# IO.net
KiCad netlist of a schematic drawn in Altium Designer
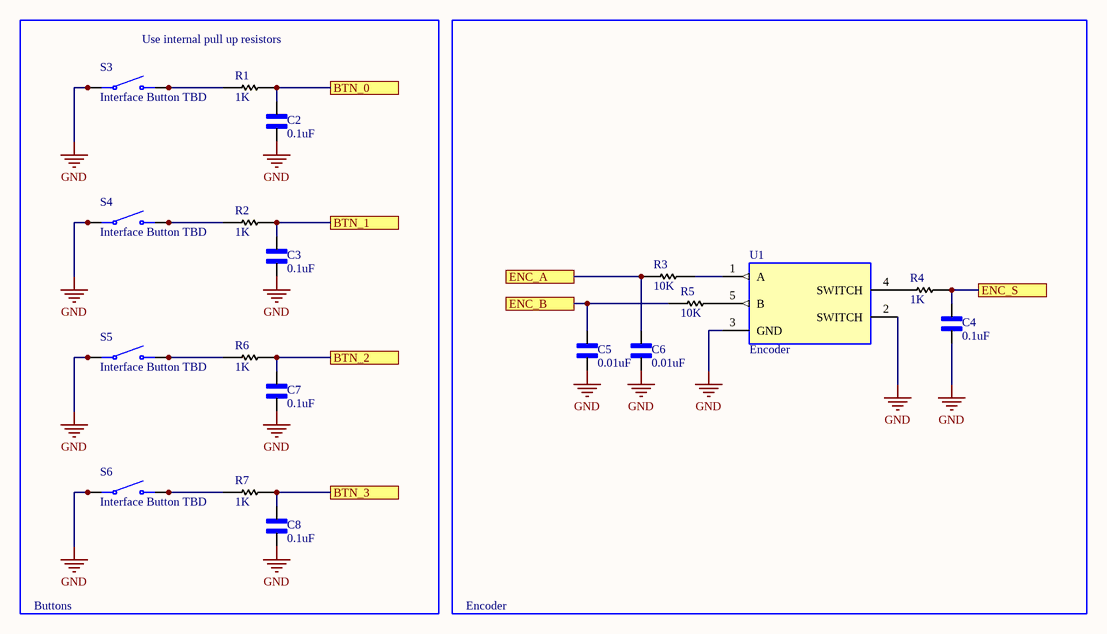
[diagram p0: IO.SchDoc]

(export (version "E")
  (design (tool "Eeschema 10.0.6"))
  (components
    (comp (ref "C2")
      (value "0.1uF")
      (footprint "CHIP_0603")
      (description "Generic 0603 Ceramic Capacitor")
      (fields (field (name "MP") "AC0402FR-071ML") (field (name "MF") "Yageo"))
      (libsource (lib "Guitar_Multi_Effect_Interface_lib") (part "0603 Ceramic Capacitor"))
    )
    (comp (ref "C3")
      (value "0.1uF")
      (footprint "CHIP_0603")
      (description "Generic 0603 Ceramic Capacitor")
      (fields (field (name "MP") "AC0402FR-071ML") (field (name "MF") "Yageo"))
      (libsource (lib "Guitar_Multi_Effect_Interface_lib") (part "0603 Ceramic Capacitor"))
    )
    (comp (ref "C4")
      (value "0.1uF")
      (footprint "CHIP_0603")
      (description "Generic 0603 Ceramic Capacitor")
      (fields (field (name "MP") "AC0402FR-071ML") (field (name "MF") "Yageo"))
      (libsource (lib "Guitar_Multi_Effect_Interface_lib") (part "0603 Ceramic Capacitor"))
    )
    (comp (ref "C5")
      (value "0.01uF")
      (footprint "CHIP_0603")
      (description "Generic 0603 Ceramic Capacitor")
      (fields (field (name "MP") "AC0402FR-071ML") (field (name "MF") "Yageo"))
      (libsource (lib "Guitar_Multi_Effect_Interface_lib") (part "0603 Ceramic Capacitor"))
    )
    (comp (ref "C6")
      (value "0.01uF")
      (footprint "CHIP_0603")
      (description "Generic 0603 Ceramic Capacitor")
      (fields (field (name "MP") "AC0402FR-071ML") (field (name "MF") "Yageo"))
      (libsource (lib "Guitar_Multi_Effect_Interface_lib") (part "0603 Ceramic Capacitor"))
    )
    (comp (ref "C7")
      (value "0.1uF")
      (footprint "CHIP_0603")
      (description "Generic 0603 Ceramic Capacitor")
      (fields (field (name "MP") "AC0402FR-071ML") (field (name "MF") "Yageo"))
      (libsource (lib "Guitar_Multi_Effect_Interface_lib") (part "0603 Ceramic Capacitor"))
    )
    (comp (ref "C8")
      (value "0.1uF")
      (footprint "CHIP_0603")
      (description "Generic 0603 Ceramic Capacitor")
      (fields (field (name "MP") "AC0402FR-071ML") (field (name "MF") "Yageo"))
      (libsource (lib "Guitar_Multi_Effect_Interface_lib") (part "0603 Ceramic Capacitor"))
    )
    (comp (ref "R1")
      (value "1K")
      (footprint "CHIP_R_0603")
      (description "Generic 0603 Resistor")
      (libsource (lib "Guitar_Multi_Effect_Interface_lib") (part "0603 Generic Resistor"))
    )
    (comp (ref "R2")
      (value "1K")
      (footprint "CHIP_R_0603")
      (description "Generic 0603 Resistor")
      (libsource (lib "Guitar_Multi_Effect_Interface_lib") (part "0603 Generic Resistor"))
    )
    (comp (ref "R3")
      (value "10K")
      (footprint "CHIP_R_0603")
      (description "Generic 0603 Resistor")
      (libsource (lib "Guitar_Multi_Effect_Interface_lib") (part "0603 Generic Resistor"))
    )
    (comp (ref "R4")
      (value "1K")
      (footprint "CHIP_R_0603")
      (description "Generic 0603 Resistor")
      (libsource (lib "Guitar_Multi_Effect_Interface_lib") (part "0603 Generic Resistor"))
    )
    (comp (ref "R5")
      (value "10K")
      (footprint "CHIP_R_0603")
      (description "Generic 0603 Resistor")
      (libsource (lib "Guitar_Multi_Effect_Interface_lib") (part "0603 Generic Resistor"))
    )
    (comp (ref "R6")
      (value "1K")
      (footprint "CHIP_R_0603")
      (description "Generic 0603 Resistor")
      (libsource (lib "Guitar_Multi_Effect_Interface_lib") (part "0603 Generic Resistor"))
    )
    (comp (ref "R7")
      (value "1K")
      (footprint "CHIP_R_0603")
      (description "Generic 0603 Resistor")
      (libsource (lib "Guitar_Multi_Effect_Interface_lib") (part "0603 Generic Resistor"))
    )
    (comp (ref "S3")
      (value "Interface Button TBD")
      (footprint "Interface_Button_Multi_Footprint")
      (description "TBD")
      (libsource (lib "Guitar_Multi_Effect_Interface_lib") (part "Interface Button TBD"))
    )
    (comp (ref "S4")
      (value "Interface Button TBD")
      (footprint "Interface_Button_Multi_Footprint")
      (description "TBD")
      (libsource (lib "Guitar_Multi_Effect_Interface_lib") (part "Interface Button TBD"))
    )
    (comp (ref "S5")
      (value "Interface Button TBD")
      (footprint "Interface_Button_Multi_Footprint")
      (description "TBD")
      (libsource (lib "Guitar_Multi_Effect_Interface_lib") (part "Interface Button TBD"))
    )
    (comp (ref "S6")
      (value "Interface Button TBD")
      (footprint "Interface_Button_Multi_Footprint")
      (description "TBD")
      (libsource (lib "Guitar_Multi_Effect_Interface_lib") (part "Interface Button TBD"))
    )
    (comp (ref "U1")
      (value "Encoder")
      (footprint "Encoder Solder Pads")
      (description "Encoder solder connections for PEC11R-4215F-S0024")
      (fields (field (name "MF") "Diodes Inc.") (field (name "MP") "AP3012KTR-G1"))
      (libsource (lib "Guitar_Multi_Effect_Interface_lib") (part "Encoder"))
    )
  )
  (nets
    (net (code "1") (name "/BTN_0") (class "Default")
      (node (ref "C2") (pin "1") (pinfunction "1_1") (pintype "passive"))
      (node (ref "R1") (pin "1") (pinfunction "1_1") (pintype "passive"))
    )
    (net (code "2") (name "/BTN_1") (class "Default")
      (node (ref "C3") (pin "1") (pinfunction "1_1") (pintype "passive"))
      (node (ref "R2") (pin "1") (pinfunction "1_1") (pintype "passive"))
    )
    (net (code "3") (name "/BTN_2") (class "Default")
      (node (ref "C7") (pin "1") (pinfunction "1_1") (pintype "passive"))
      (node (ref "R6") (pin "1") (pinfunction "1_1") (pintype "passive"))
    )
    (net (code "4") (name "/BTN_3") (class "Default")
      (node (ref "C8") (pin "1") (pinfunction "1_1") (pintype "passive"))
      (node (ref "R7") (pin "1") (pinfunction "1_1") (pintype "passive"))
    )
    (net (code "5") (name "/ENC_A") (class "Default")
      (node (ref "C6") (pin "1") (pinfunction "1_1") (pintype "passive"))
      (node (ref "R3") (pin "2") (pinfunction "2_2") (pintype "passive"))
    )
    (net (code "6") (name "/ENC_B") (class "Default")
      (node (ref "C5") (pin "1") (pinfunction "1_1") (pintype "passive"))
      (node (ref "R5") (pin "2") (pinfunction "2_2") (pintype "passive"))
    )
    (net (code "7") (name "/ENC_S") (class "Default")
      (node (ref "C4") (pin "1") (pinfunction "1_1") (pintype "passive"))
      (node (ref "R4") (pin "1") (pinfunction "1_1") (pintype "passive"))
    )
    (net (code "8") (name "GND") (class "Default")
      (node (ref "C2") (pin "2") (pinfunction "2_2") (pintype "passive"))
      (node (ref "C3") (pin "2") (pinfunction "2_2") (pintype "passive"))
      (node (ref "C4") (pin "2") (pinfunction "2_2") (pintype "passive"))
      (node (ref "C5") (pin "2") (pinfunction "2_2") (pintype "passive"))
      (node (ref "C6") (pin "2") (pinfunction "2_2") (pintype "passive"))
      (node (ref "C7") (pin "2") (pinfunction "2_2") (pintype "passive"))
      (node (ref "C8") (pin "2") (pinfunction "2_2") (pintype "passive"))
      (node (ref "S3") (pin "1") (pinfunction "COM_1") (pintype "passive"))
      (node (ref "S3") (pin "2") (pinfunction "COM_2") (pintype "passive"))
      (node (ref "S4") (pin "1") (pinfunction "COM_1") (pintype "passive"))
      (node (ref "S4") (pin "2") (pinfunction "COM_2") (pintype "passive"))
      (node (ref "S5") (pin "1") (pinfunction "COM_1") (pintype "passive"))
      (node (ref "S5") (pin "2") (pinfunction "COM_2") (pintype "passive"))
      (node (ref "S6") (pin "1") (pinfunction "COM_1") (pintype "passive"))
      (node (ref "S6") (pin "2") (pinfunction "COM_2") (pintype "passive"))
      (node (ref "U1") (pin "2") (pinfunction "SWITCH_2") (pintype "passive"))
      (node (ref "U1") (pin "3") (pinfunction "GND_3") (pintype "power_in"))
    )
    (net (code "9") (name "Net-(R1-Pad2)") (class "Default")
      (node (ref "R1") (pin "2") (pinfunction "2_2") (pintype "passive"))
      (node (ref "S3") (pin "3") (pinfunction "NO_3") (pintype "passive"))
      (node (ref "S3") (pin "4") (pinfunction "NO_4") (pintype "passive"))
    )
    (net (code "10") (name "Net-(R2-Pad2)") (class "Default")
      (node (ref "R2") (pin "2") (pinfunction "2_2") (pintype "passive"))
      (node (ref "S4") (pin "3") (pinfunction "NO_3") (pintype "passive"))
      (node (ref "S4") (pin "4") (pinfunction "NO_4") (pintype "passive"))
    )
    (net (code "11") (name "Net-(R4-Pad2)") (class "Default")
      (node (ref "R4") (pin "2") (pinfunction "2_2") (pintype "passive"))
      (node (ref "U1") (pin "4") (pinfunction "SWITCH_4") (pintype "passive"))
    )
    (net (code "12") (name "Net-(R6-Pad2)") (class "Default")
      (node (ref "R6") (pin "2") (pinfunction "2_2") (pintype "passive"))
      (node (ref "S5") (pin "3") (pinfunction "NO_3") (pintype "passive"))
      (node (ref "S5") (pin "4") (pinfunction "NO_4") (pintype "passive"))
    )
    (net (code "13") (name "Net-(R7-Pad2)") (class "Default")
      (node (ref "R7") (pin "2") (pinfunction "2_2") (pintype "passive"))
      (node (ref "S6") (pin "3") (pinfunction "NO_3") (pintype "passive"))
      (node (ref "S6") (pin "4") (pinfunction "NO_4") (pintype "passive"))
    )
    (net (code "14") (name "Net-(U1-A)") (class "Default")
      (node (ref "R3") (pin "1") (pinfunction "1_1") (pintype "passive"))
      (node (ref "U1") (pin "1") (pinfunction "A_1") (pintype "output"))
    )
    (net (code "15") (name "Net-(U1-B)") (class "Default")
      (node (ref "R5") (pin "1") (pinfunction "1_1") (pintype "passive"))
      (node (ref "U1") (pin "5") (pinfunction "B_5") (pintype "output"))
    )
  )
)
